# BuckRegulator-5V.net
KiCad netlist of a schematic drawn in Altium Designer
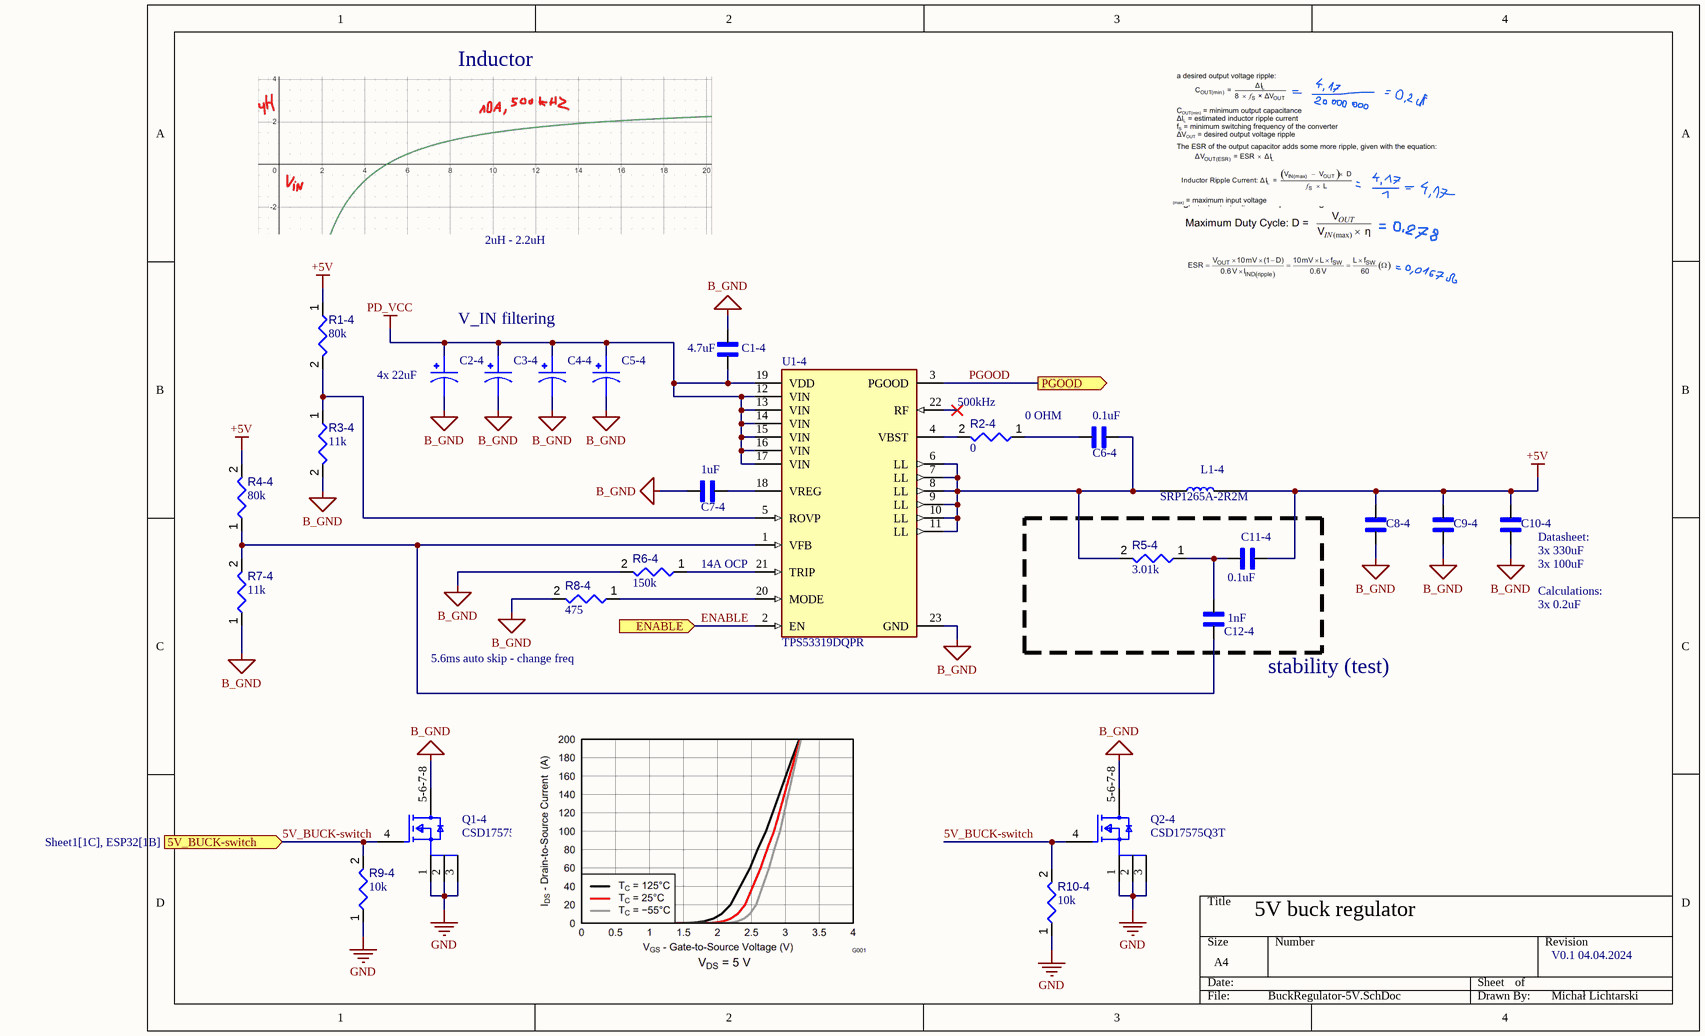
[diagram p0: BuckRegulator-5V.SchDoc]

(export (version "E")
  (design (tool "Eeschema 10.0.6"))
  (components
    (comp (ref "C1-4")
      (value "4.7uF 0805 35V")
      (footprint "CL21A475KLCLQNC:CAPC2012X135N")
      (fields (field (name "MF") "{'manufacturer': u'Samsung'}") (field (name "MP") "CL21A475KLCLQNC"))
      (libsource (lib "*") (part "CL21A475KLCLQNC"))
    )
    (comp (ref "C2-4")
      (value "TCJD226M035R0070")
      (footprint "TPSD107M016S0100:CAPPM7343X310N")
      (description "CAP TANT POLY 22UF 35V 2917")
      (fields (field (name "MF") "{'manufacturer': u'AVX'}") (field (name "MP") "TPSD107M016S0100"))
      (libsource (lib "*") (part "TPSD107M016S0100"))
    )
    (comp (ref "C3-4")
      (value "TCJD226M035R0070")
      (footprint "TPSD107M016S0100:CAPPM7343X310N")
      (description "CAP TANT POLY 22UF 35V 2917")
      (fields (field (name "MF") "{'manufacturer': u'AVX'}") (field (name "MP") "TPSD107M016S0100"))
      (libsource (lib "*") (part "TPSD107M016S0100"))
    )
    (comp (ref "C4-4")
      (value "TCJD226M035R0070")
      (footprint "TPSD107M016S0100:CAPPM7343X310N")
      (description "CAP TANT POLY 22UF 35V 2917")
      (fields (field (name "MF") "{'manufacturer': u'AVX'}") (field (name "MP") "TPSD107M016S0100"))
      (libsource (lib "*") (part "TPSD107M016S0100"))
    )
    (comp (ref "C5-4")
      (value "TCJD226M035R0070")
      (footprint "TPSD107M016S0100:CAPPM7343X310N")
      (description "CAP TANT POLY 22UF 35V 2917")
      (fields (field (name "MF") "{'manufacturer': u'AVX'}") (field (name "MP") "TPSD107M016S0100"))
      (libsource (lib "*") (part "TPSD107M016S0100"))
    )
    (comp (ref "C6-4")
      (value "0.1uF 0603")
      (footprint "CL10B104KB8NNNC:CAPC1608X90N")
      (fields
        (field (name "MF") "{'manufacturer': u'Samsung Electro-Mechanics'}")
        (field (name "MP") "CL10B104KB8NNNC")
      )
      (libsource (lib "*") (part "CL10B104KB8NNNC"))
    )
    (comp (ref "C7-4")
      (value "1uF 0603")
      (footprint "CL21B105KBFNNNE:CAPC2012X140N")
      (fields
        (field (name "MF") "{'manufacturer': u'Samsung Electro-Mechanics'}")
        (field (name "MP") "CL21B105KBFNNNE")
      )
      (libsource (lib "*") (part "CL21B105KBFNNNE"))
    )
    (comp (ref "C8-4")
      (value "100uF 10V 1210")
      (footprint "CL32A107MPVNNNE:ANTC3225X280N")
      (description "Cap Ceramic 100uF 10V X5R 20% SMD 1210 85Â°C Embossed T/R")
      (fields
        (field (name "MF") "{'manufacturer': u'Samsung Electro-Mechanics'}")
        (field (name "MP") "CL32A107MPVNNNE")
      )
      (libsource (lib "*") (part "CL32A107MPVNNNE"))
    )
    (comp (ref "C9-4")
      (value "100uF 10V 1210")
      (footprint "CL32A107MPVNNNE:ANTC3225X280N")
      (description "Cap Ceramic 100uF 10V X5R 20% SMD 1210 85Â°C Embossed T/R")
      (fields
        (field (name "MF") "{'manufacturer': u'Samsung Electro-Mechanics'}")
        (field (name "MP") "CL32A107MPVNNNE")
      )
      (libsource (lib "*") (part "CL32A107MPVNNNE"))
    )
    (comp (ref "C10-4")
      (value "100uF 10V 1210")
      (footprint "CL32A107MPVNNNE:ANTC3225X280N")
      (description "Cap Ceramic 100uF 10V X5R 20% SMD 1210 85Â°C Embossed T/R")
      (fields
        (field (name "MF") "{'manufacturer': u'Samsung Electro-Mechanics'}")
        (field (name "MP") "CL32A107MPVNNNE")
      )
      (libsource (lib "*") (part "CL32A107MPVNNNE"))
    )
    (comp (ref "C11-4")
      (value "0.1uF 0603")
      (footprint "CL10B104KB8NNNC:CAPC1608X90N")
      (fields
        (field (name "MF") "{'manufacturer': u'Samsung Electro-Mechanics'}")
        (field (name "MP") "CL10B104KB8NNNC")
      )
      (libsource (lib "*") (part "CL10B104KB8NNNC"))
    )
    (comp (ref "C12-4")
      (value "1uF 0603")
      (footprint "CL10B104KB8NNNC:CAPC1608X90N")
      (fields
        (field (name "MF") "{'manufacturer': u'Samsung Electro-Mechanics'}")
        (field (name "MP") "CL10B104KB8NNNC")
      )
      (libsource (lib "") (part "CL10B104KB8NNNC_1"))
    )
    (comp (ref "L1-4")
      (value "SRP1265A-2R2M")
      (footprint "SRP1265A-330M:IND_SRP1265A-330M")
      (description "Inductor Power Shielded Wirewound 33uH 20% 100KHz Carbonyl Powder 8A 58mOhm DCR Automotive T/R")
      (fields (field (name "MF") "{'manufacturer': u'Bourns'}") (field (name "MP") "SRP1265A-330M"))
      (libsource (lib "*") (part "SRP1265A-330M"))
    )
    (comp (ref "Q1-4")
      (value "CSD17575Q3T")
      (footprint "FP-DQG0008A-MFG")
      (description "MOSFET N-CH 30V 60A 8VSON")
      (libsource (lib "Altium Content Vault") (part "67ab74940b0fb01b7d29851f779ca15"))
    )
    (comp (ref "Q2-4")
      (value "CSD17575Q3T")
      (footprint "FP-DQG0008A-MFG")
      (description "MOSFET N-CH 30V 60A 8VSON")
      (libsource (lib "Altium Content Vault") (part "67ab74940b0fb01b7d29851f779ca15"))
    )
    (comp (ref "R1-4")
      (value "80k")
      (footprint "RESC1608X55X25ML10T15")
      (fields
        (field (name "TOLERANCE") "1%")
        (field (name "POWER") "100mW")
        (field (name "Comment") "80k 0603")
      )
      (libsource (lib "Michal") (part "RES-2"))
    )
    (comp (ref "R2-4")
      (value "0")
      (footprint "RESC1608X55X25ML10T15")
      (fields
        (field (name "TOLERANCE") "1%")
        (field (name "POWER") "100mW")
        (field (name "Comment") "0 0603")
      )
      (libsource (lib "Michal") (part "RES-2"))
    )
    (comp (ref "R3-4")
      (value "11k")
      (footprint "RESC1608X55X25ML10T15")
      (fields
        (field (name "TOLERANCE") "1%")
        (field (name "POWER") "100mW")
        (field (name "Comment") "11k 0603")
      )
      (libsource (lib "Michal") (part "RES-2"))
    )
    (comp (ref "R4-4")
      (value "80k")
      (footprint "RESC1608X55X25ML10T15")
      (fields
        (field (name "TOLERANCE") "1%")
        (field (name "POWER") "100mW")
        (field (name "Comment") "80k 0603")
      )
      (libsource (lib "Michal") (part "RES-2"))
    )
    (comp (ref "R5-4")
      (value "3.01k")
      (footprint "RESC1608X55X25ML10T15")
      (fields
        (field (name "TOLERANCE") "1%")
        (field (name "POWER") "100mW")
        (field (name "Comment") "3.01k 0603")
      )
      (libsource (lib "Michal") (part "RES-2"))
    )
    (comp (ref "R6-4")
      (value "150k")
      (footprint "RESC1608X55X25ML10T15")
      (fields
        (field (name "TOLERANCE") "1%")
        (field (name "POWER") "100mW")
        (field (name "Comment") "150k 0603")
      )
      (libsource (lib "Michal") (part "RES-2"))
    )
    (comp (ref "R7-4")
      (value "11k")
      (footprint "RESC1608X55X25ML10T15")
      (fields
        (field (name "TOLERANCE") "1%")
        (field (name "POWER") "100mW")
        (field (name "Comment") "11k 0603")
      )
      (libsource (lib "Michal") (part "RES-2"))
    )
    (comp (ref "R8-4")
      (value "475")
      (footprint "RESC1608X55X25ML10T15")
      (description "Chip Resistor, 4.7 KOhm, +/- 1%, 0.1 W, -55 to 155 degC, 0603 (1608 Metric)")
      (fields (field (name "TOLERANCE") "1%") (field (name "POWER") "100mW"))
      (libsource (lib "Michal") (part "RES-2"))
    )
    (comp (ref "R9-4")
      (value "10k")
      (footprint "RESC1608X55X25ML10T15")
      (fields
        (field (name "TOLERANCE") "1%")
        (field (name "POWER") "100mW")
        (field (name "Comment") "10k 0603")
      )
      (libsource (lib "Michal") (part "RES-2"))
    )
    (comp (ref "R10-4")
      (value "10k")
      (footprint "RESC1608X55X25ML10T15")
      (description "Chip Resistor, 4.7 KOhm, +/- 1%, 0.1 W, -55 to 155 degC, 0603 (1608 Metric)")
      (fields (field (name "TOLERANCE") "1%") (field (name "POWER") "100mW"))
      (libsource (lib "Michal") (part "RES-2"))
    )
    (comp (ref "U1-4")
      (value "TPS53319DQPR")
      (footprint "FP-DQP0022A-MFG")
      (description "IC REG BUCK ADJUSTABLE 14A 22SON")
      (libsource (lib "Altium Content Vault") (part "dba826845fdfa018faa42a689150bd3"))
    )
  )
  (nets
    (net (code "1") (name "+5V") (class "Default")
      (node (ref "C10-4") (pin "1") (pinfunction "1_1") (pintype "passive"))
      (node (ref "C11-4") (pin "1") (pinfunction "1_1") (pintype "passive"))
      (node (ref "C8-4") (pin "1") (pinfunction "1_1") (pintype "passive"))
      (node (ref "C9-4") (pin "1") (pinfunction "1_1") (pintype "passive"))
      (node (ref "L1-4") (pin "2") (pinfunction "2_2") (pintype "passive"))
      (node (ref "R1-4") (pin "1") (pinfunction "1_1") (pintype "passive"))
      (node (ref "R4-4") (pin "2") (pinfunction "2_2") (pintype "passive"))
    )
    (net (code "2") (name "/5V_BUCK-switch") (class "Default")
      (node (ref "Q1-4") (pin "4") (pinfunction "G_4") (pintype "passive"))
      (node (ref "Q2-4") (pin "4") (pinfunction "G_4") (pintype "passive"))
      (node (ref "R10-4") (pin "2") (pinfunction "2_2") (pintype "passive"))
      (node (ref "R9-4") (pin "2") (pinfunction "2_2") (pintype "passive"))
    )
    (net (code "3") (name "/ENABLE") (class "Default")
      (node (ref "U1-4") (pin "2") (pinfunction "EN_2") (pintype "input"))
    )
    (net (code "4") (name "/PGOOD") (class "Default")
      (node (ref "U1-4") (pin "3") (pinfunction "PGOOD_3") (pintype "open_collector"))
    )
    (net (code "5") (name "B_GND") (class "Default")
      (node (ref "C1-4") (pin "1") (pinfunction "1_1") (pintype "passive"))
      (node (ref "C10-4") (pin "2") (pinfunction "2_2") (pintype "passive"))
      (node (ref "C2-4") (pin "2") (pinfunction "2_2") (pintype "passive"))
      (node (ref "C3-4") (pin "2") (pinfunction "2_2") (pintype "passive"))
      (node (ref "C4-4") (pin "2") (pinfunction "2_2") (pintype "passive"))
      (node (ref "C5-4") (pin "2") (pinfunction "2_2") (pintype "passive"))
      (node (ref "C7-4") (pin "1") (pinfunction "1_1") (pintype "passive"))
      (node (ref "C8-4") (pin "2") (pinfunction "2_2") (pintype "passive"))
      (node (ref "C9-4") (pin "2") (pinfunction "2_2") (pintype "passive"))
      (node (ref "Q1-4") (pin "5-6-7-8") (pinfunction "D_5-6-7-8") (pintype "passive"))
      (node (ref "Q2-4") (pin "5-6-7-8") (pinfunction "D_5-6-7-8") (pintype "passive"))
      (node (ref "R3-4") (pin "2") (pinfunction "2_2") (pintype "passive"))
      (node (ref "R6-4") (pin "2") (pinfunction "2_2") (pintype "passive"))
      (node (ref "R7-4") (pin "1") (pinfunction "1_1") (pintype "passive"))
      (node (ref "R8-4") (pin "2") (pinfunction "2_2") (pintype "passive"))
      (node (ref "U1-4") (pin "23") (pinfunction "GND_23") (pintype "power_in"))
    )
    (net (code "6") (name "GND") (class "Default")
      (node (ref "Q1-4") (pin "1") (pinfunction "S_1") (pintype "passive"))
      (node (ref "Q1-4") (pin "2") (pinfunction "S_2") (pintype "passive"))
      (node (ref "Q1-4") (pin "3") (pinfunction "S_3") (pintype "passive"))
      (node (ref "Q2-4") (pin "1") (pinfunction "S_1") (pintype "passive"))
      (node (ref "Q2-4") (pin "2") (pinfunction "S_2") (pintype "passive"))
      (node (ref "Q2-4") (pin "3") (pinfunction "S_3") (pintype "passive"))
      (node (ref "R10-4") (pin "1") (pinfunction "1_1") (pintype "passive"))
      (node (ref "R9-4") (pin "1") (pinfunction "1_1") (pintype "passive"))
    )
    (net (code "7") (name "Net-(C6-4-Pad1)") (class "Default")
      (node (ref "C6-4") (pin "1") (pinfunction "1_1") (pintype "passive"))
      (node (ref "L1-4") (pin "1") (pinfunction "1_1") (pintype "passive"))
      (node (ref "R5-4") (pin "2") (pinfunction "2_2") (pintype "passive"))
      (node (ref "U1-4") (pin "10") (pinfunction "LL_10") (pintype "output"))
      (node (ref "U1-4") (pin "11") (pinfunction "LL_11") (pintype "output"))
      (node (ref "U1-4") (pin "6") (pinfunction "LL_6") (pintype "output"))
      (node (ref "U1-4") (pin "7") (pinfunction "LL_7") (pintype "output"))
      (node (ref "U1-4") (pin "8") (pinfunction "LL_8") (pintype "output"))
      (node (ref "U1-4") (pin "9") (pinfunction "LL_9") (pintype "output"))
    )
    (net (code "8") (name "Net-(C6-4-Pad2)") (class "Default")
      (node (ref "C6-4") (pin "2") (pinfunction "2_2") (pintype "passive"))
      (node (ref "R2-4") (pin "1") (pinfunction "1_1") (pintype "passive"))
    )
    (net (code "9") (name "Net-(C11-4-Pad2)") (class "Default")
      (node (ref "C11-4") (pin "2") (pinfunction "2_2") (pintype "passive"))
      (node (ref "C12-4") (pin "1") (pinfunction "1_1") (pintype "passive"))
      (node (ref "R5-4") (pin "1") (pinfunction "1_1") (pintype "passive"))
    )
    (net (code "10") (name "Net-(U1-4-MODE)") (class "Default")
      (node (ref "R8-4") (pin "1") (pinfunction "1_1") (pintype "passive"))
      (node (ref "U1-4") (pin "20") (pinfunction "MODE_20") (pintype "input"))
    )
    (net (code "11") (name "Net-(U1-4-ROVP)") (class "Default")
      (node (ref "R1-4") (pin "2") (pinfunction "2_2") (pintype "passive"))
      (node (ref "R3-4") (pin "1") (pinfunction "1_1") (pintype "passive"))
      (node (ref "U1-4") (pin "5") (pinfunction "ROVP_5") (pintype "input"))
    )
    (net (code "12") (name "Net-(U1-4-TRIP)") (class "Default")
      (node (ref "R6-4") (pin "1") (pinfunction "1_1") (pintype "passive"))
      (node (ref "U1-4") (pin "21") (pinfunction "TRIP_21") (pintype "input"))
    )
    (net (code "13") (name "Net-(U1-4-VBST)") (class "Default")
      (node (ref "R2-4") (pin "2") (pinfunction "2_2") (pintype "passive"))
      (node (ref "U1-4") (pin "4") (pinfunction "VBST_4") (pintype "power_in"))
    )
    (net (code "14") (name "Net-(U1-4-VFB)") (class "Default")
      (node (ref "C12-4") (pin "2") (pinfunction "2_2") (pintype "passive"))
      (node (ref "R4-4") (pin "1") (pinfunction "1_1") (pintype "passive"))
      (node (ref "R7-4") (pin "2") (pinfunction "2_2") (pintype "passive"))
      (node (ref "U1-4") (pin "1") (pinfunction "VFB_1") (pintype "input"))
    )
    (net (code "15") (name "Net-(U1-4-VREG)") (class "Default")
      (node (ref "C7-4") (pin "2") (pinfunction "2_2") (pintype "passive"))
      (node (ref "U1-4") (pin "18") (pinfunction "VREG_18") (pintype "power_in"))
    )
    (net (code "16") (name "PD_VCC") (class "Default")
      (node (ref "C1-4") (pin "2") (pinfunction "2_2") (pintype "passive"))
      (node (ref "C2-4") (pin "1") (pinfunction "1_1") (pintype "passive"))
      (node (ref "C3-4") (pin "1") (pinfunction "1_1") (pintype "passive"))
      (node (ref "C4-4") (pin "1") (pinfunction "1_1") (pintype "passive"))
      (node (ref "C5-4") (pin "1") (pinfunction "1_1") (pintype "passive"))
      (node (ref "U1-4") (pin "12") (pinfunction "VIN_12") (pintype "power_in"))
      (node (ref "U1-4") (pin "13") (pinfunction "VIN_13") (pintype "power_in"))
      (node (ref "U1-4") (pin "14") (pinfunction "VIN_14") (pintype "power_in"))
      (node (ref "U1-4") (pin "15") (pinfunction "VIN_15") (pintype "power_in"))
      (node (ref "U1-4") (pin "16") (pinfunction "VIN_16") (pintype "power_in"))
      (node (ref "U1-4") (pin "17") (pinfunction "VIN_17") (pintype "power_in"))
      (node (ref "U1-4") (pin "19") (pinfunction "VDD_19") (pintype "power_in"))
    )
    (net (code "17") (name "unconnected-(U1-4-RF-Pad22)") (class "Default")
      (node (ref "U1-4") (pin "22") (pinfunction "RF_22") (pintype "input+no_connect"))
    )
  )
)
